# DCO_core_1_0.net
KiCad netlist of a schematic drawn in EAGLE
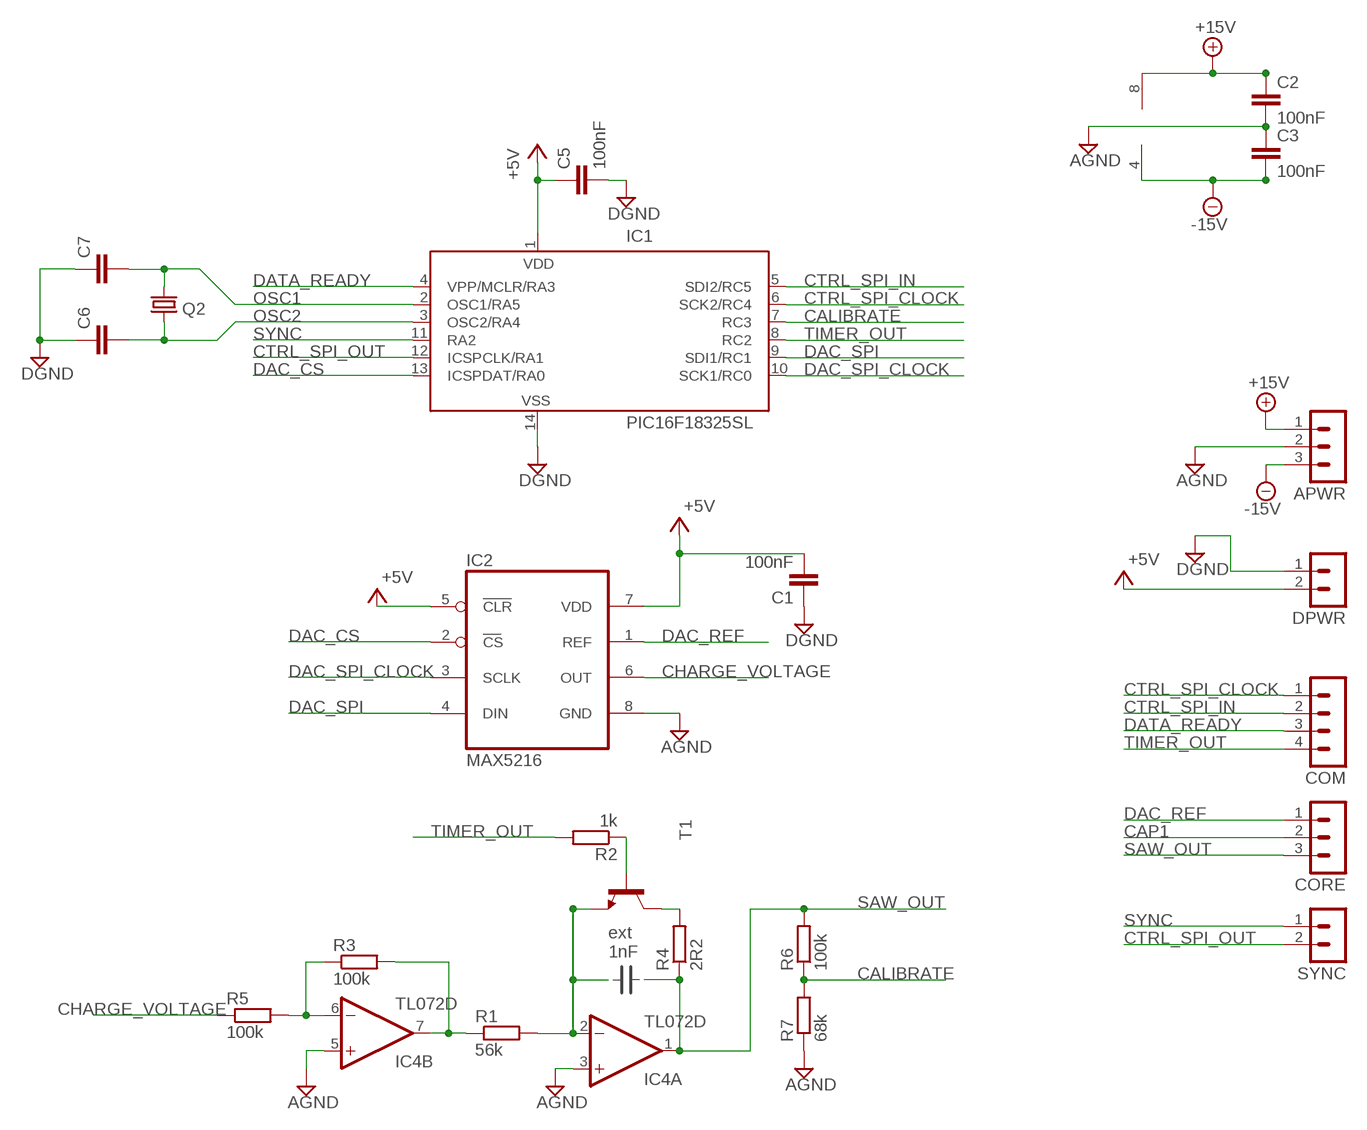
[diagram p0: schematic, sheet 1]

(export (version "E")
  (design (tool "Eeschema 10.0.6"))
  (components
    (comp (ref "APWR")
      (value "MA03-1JP")
      (footprint "eagle-import:SIP-PIN03-1J")
      (libsource (lib "eagle-import") (part "MA03-1JP"))
    )
    (comp (ref "C1")
      (value "100nF")
      (footprint "eagle-import:C0805")
      (libsource (lib "eagle-import") (part "C-EUC0805"))
    )
    (comp (ref "C2")
      (value "100nF")
      (footprint "eagle-import:C0805")
      (libsource (lib "eagle-import") (part "C-EUC0805"))
    )
    (comp (ref "C3")
      (value "100nF")
      (footprint "eagle-import:C0805")
      (libsource (lib "eagle-import") (part "C-EUC0805"))
    )
    (comp (ref "C5")
      (value "100nF")
      (footprint "eagle-import:C0805")
      (libsource (lib "eagle-import") (part "C-EUC0805"))
    )
    (comp (ref "C6")
      (value "C-EUC0805")
      (footprint "eagle-import:C0805")
      (libsource (lib "eagle-import") (part "C-EUC0805"))
    )
    (comp (ref "C7")
      (value "C-EUC0805")
      (footprint "eagle-import:C0805")
      (libsource (lib "eagle-import") (part "C-EUC0805"))
    )
    (comp (ref "COM")
      (value "MA04-1JP")
      (footprint "eagle-import:SIP-PIN04-1J")
      (libsource (lib "eagle-import") (part "MA04-1JP"))
    )
    (comp (ref "CORE")
      (value "MA03-1JP")
      (footprint "eagle-import:SIP-PIN03-1J")
      (libsource (lib "eagle-import") (part "MA03-1JP"))
    )
    (comp (ref "DPWR")
      (value "MA02-1JP")
      (footprint "eagle-import:SIP-PIN02-1J")
      (libsource (lib "eagle-import") (part "MA02-1JP"))
    )
    (comp (ref "IC1")
      (value "PIC16F18325SL")
      (footprint "eagle-import:SO14J")
      (fields (field (name "MF") "MICROCHIP") (field (name "MPN") "PIC16F676-I/SL"))
      (libsource (lib "eagle-import") (part "PIC16F18325SL"))
    )
    (comp (ref "IC2")
      (value "MAX5216")
      (footprint "eagle-import:UMAX8J")
      (libsource (lib "eagle-import") (part "MAX5216"))
    )
    (comp (ref "IC4")
      (value "TL072D")
      (footprint "eagle-import:SO08J")
      (libsource (lib "eagle-import") (part "TL072D"))
    )
    (comp (ref "Q2")
      (value "CRYSTALHC49S")
      (footprint "eagle-import:HC49_S")
      (libsource (lib "eagle-import") (part "CRYSTALHC49S"))
    )
    (comp (ref "R1")
      (value "56k")
      (footprint "eagle-import:R0805")
      (libsource (lib "eagle-import") (part "R-EU_R0805"))
    )
    (comp (ref "R2")
      (value "1k")
      (footprint "eagle-import:R0805")
      (libsource (lib "eagle-import") (part "R-EU_R0805"))
    )
    (comp (ref "R3")
      (value "100k")
      (footprint "eagle-import:R0805")
      (libsource (lib "eagle-import") (part "R-EU_R0805"))
    )
    (comp (ref "R4")
      (value "2R2")
      (footprint "eagle-import:R0805")
      (libsource (lib "eagle-import") (part "R-EU_R0805"))
    )
    (comp (ref "R5")
      (value "100k")
      (footprint "eagle-import:R0805")
      (libsource (lib "eagle-import") (part "R-EU_R0805"))
    )
    (comp (ref "R6")
      (value "100k")
      (footprint "eagle-import:R0805")
      (libsource (lib "eagle-import") (part "R-EU_R0805"))
    )
    (comp (ref "R7")
      (value "68k")
      (footprint "eagle-import:R0805")
      (libsource (lib "eagle-import") (part "R-EU_R0805"))
    )
    (comp (ref "SYNC")
      (value "MA02-1JP")
      (footprint "eagle-import:SIP-PIN02-1J")
      (libsource (lib "eagle-import") (part "MA02-1JP"))
    )
    (comp (ref "T1")
      (value "MMBT3904LT1-NPN-SOT23-BEC")
      (footprint "eagle-import:SOT23-BEC")
      (libsource (lib "eagle-import") (part "-NPN-SOT23-BECMMBT3904LT1"))
    )
  )
  (nets
    (net (code "1") (name "+5V") (class "Default")
      (node (ref "C1") (pin "2") (pinfunction "2_2") (pintype "passive"))
      (node (ref "C5") (pin "1") (pinfunction "1_1") (pintype "passive"))
      (node (ref "DPWR") (pin "2") (pinfunction "2_2") (pintype "passive"))
      (node (ref "IC1") (pin "1") (pinfunction "VDD_1") (pintype "power_in"))
      (node (ref "IC2") (pin "5") (pinfunction "CLR_5") (pintype "input"))
      (node (ref "IC2") (pin "7") (pinfunction "VDD_7") (pintype "power_in"))
    )
    (net (code "2") (name "+15V") (class "Default")
      (node (ref "APWR") (pin "1") (pinfunction "1_1") (pintype "passive"))
      (node (ref "C2") (pin "1") (pinfunction "1_1") (pintype "passive"))
      (node (ref "IC4") (pin "8") (pinfunction "V+_8") (pintype "power_in"))
    )
    (net (code "3") (name "-15V") (class "Default")
      (node (ref "APWR") (pin "3") (pinfunction "3_3") (pintype "passive"))
      (node (ref "C3") (pin "2") (pinfunction "2_2") (pintype "passive"))
      (node (ref "IC4") (pin "4") (pinfunction "V-_4") (pintype "power_in"))
    )
    (net (code "4") (name "/CALIBRATE") (class "Default")
      (node (ref "IC1") (pin "7") (pinfunction "RC3_7") (pintype "bidirectional"))
      (node (ref "R6") (pin "1") (pinfunction "1_1") (pintype "passive"))
      (node (ref "R7") (pin "2") (pinfunction "2_2") (pintype "passive"))
    )
    (net (code "5") (name "/CAP1") (class "Default")
      (node (ref "CORE") (pin "2") (pinfunction "2_2") (pintype "passive"))
      (node (ref "IC4") (pin "2") (pinfunction "-IN_2") (pintype "input"))
      (node (ref "R1") (pin "2") (pinfunction "2_2") (pintype "passive"))
      (node (ref "T1") (pin "E") (pinfunction "E_E") (pintype "passive"))
    )
    (net (code "6") (name "/CHARGE_VOLTAGE") (class "Default")
      (node (ref "IC2") (pin "6") (pinfunction "OUT_6") (pintype "power_in"))
      (node (ref "R5") (pin "1") (pinfunction "1_1") (pintype "passive"))
    )
    (net (code "7") (name "/CTRL_SPI_CLOCK") (class "Default")
      (node (ref "COM") (pin "1") (pinfunction "1_1") (pintype "passive"))
      (node (ref "IC1") (pin "6") (pinfunction "SCK2/RC4_6") (pintype "bidirectional"))
    )
    (net (code "8") (name "/CTRL_SPI_IN") (class "Default")
      (node (ref "COM") (pin "2") (pinfunction "2_2") (pintype "passive"))
      (node (ref "IC1") (pin "5") (pinfunction "SDI2/RC5_5") (pintype "bidirectional"))
    )
    (net (code "9") (name "/CTRL_SPI_OUT") (class "Default")
      (node (ref "IC1") (pin "12") (pinfunction "ICSPCLK/RA1_12") (pintype "bidirectional"))
      (node (ref "SYNC") (pin "2") (pinfunction "2_2") (pintype "passive"))
    )
    (net (code "10") (name "/DAC_CS") (class "Default")
      (node (ref "IC1") (pin "13") (pinfunction "ICSPDAT/RA0_13") (pintype "bidirectional"))
      (node (ref "IC2") (pin "2") (pinfunction "CS_2") (pintype "input"))
    )
    (net (code "11") (name "/DAC_REF") (class "Default")
      (node (ref "CORE") (pin "1") (pinfunction "1_1") (pintype "passive"))
      (node (ref "IC2") (pin "1") (pinfunction "REF_1") (pintype "input"))
    )
    (net (code "12") (name "/DAC_SPI") (class "Default")
      (node (ref "IC1") (pin "9") (pinfunction "SDI1/RC1_9") (pintype "bidirectional"))
      (node (ref "IC2") (pin "4") (pinfunction "DIN_4") (pintype "input"))
    )
    (net (code "13") (name "/DAC_SPI_CLOCK") (class "Default")
      (node (ref "IC1") (pin "10") (pinfunction "SCK1/RC0_10") (pintype "bidirectional"))
      (node (ref "IC2") (pin "3") (pinfunction "SCLK_3") (pintype "input"))
    )
    (net (code "14") (name "/DATA_READY") (class "Default")
      (node (ref "COM") (pin "3") (pinfunction "3_3") (pintype "passive"))
      (node (ref "IC1") (pin "4") (pinfunction "VPP/MCLR/RA3_4") (pintype "input"))
    )
    (net (code "15") (name "/OSC1") (class "Default")
      (node (ref "C7") (pin "2") (pinfunction "2_2") (pintype "passive"))
      (node (ref "IC1") (pin "2") (pinfunction "OSC1/RA5_2") (pintype "bidirectional"))
      (node (ref "Q2") (pin "2") (pinfunction "2_2") (pintype "passive"))
    )
    (net (code "16") (name "/OSC2") (class "Default")
      (node (ref "C6") (pin "2") (pinfunction "2_2") (pintype "passive"))
      (node (ref "IC1") (pin "3") (pinfunction "OSC2/RA4_3") (pintype "bidirectional"))
      (node (ref "Q2") (pin "1") (pinfunction "1_1") (pintype "passive"))
    )
    (net (code "17") (name "/SAW_OUT") (class "Default")
      (node (ref "CORE") (pin "3") (pinfunction "3_3") (pintype "passive"))
      (node (ref "IC4") (pin "1") (pinfunction "OUT_1") (pintype "output"))
      (node (ref "R4") (pin "1") (pinfunction "1_1") (pintype "passive"))
      (node (ref "R6") (pin "2") (pinfunction "2_2") (pintype "passive"))
    )
    (net (code "18") (name "/SYNC") (class "Default")
      (node (ref "IC1") (pin "11") (pinfunction "RA2_11") (pintype "bidirectional"))
      (node (ref "SYNC") (pin "1") (pinfunction "1_1") (pintype "passive"))
    )
    (net (code "19") (name "/TIMER_OUT") (class "Default")
      (node (ref "COM") (pin "4") (pinfunction "4_4") (pintype "passive"))
      (node (ref "IC1") (pin "8") (pinfunction "RC2_8") (pintype "bidirectional"))
      (node (ref "R2") (pin "2") (pinfunction "2_2") (pintype "passive"))
    )
    (net (code "20") (name "AGND") (class "Default")
      (node (ref "APWR") (pin "2") (pinfunction "2_2") (pintype "passive"))
      (node (ref "C2") (pin "2") (pinfunction "2_2") (pintype "passive"))
      (node (ref "C3") (pin "1") (pinfunction "1_1") (pintype "passive"))
      (node (ref "IC2") (pin "8") (pinfunction "GND_8") (pintype "power_in"))
      (node (ref "IC4") (pin "3") (pinfunction "+IN_3") (pintype "input"))
      (node (ref "IC4") (pin "5") (pinfunction "+IN_5") (pintype "input"))
      (node (ref "R7") (pin "1") (pinfunction "1_1") (pintype "passive"))
    )
    (net (code "21") (name "DGND") (class "Default")
      (node (ref "C1") (pin "1") (pinfunction "1_1") (pintype "passive"))
      (node (ref "C5") (pin "2") (pinfunction "2_2") (pintype "passive"))
      (node (ref "C6") (pin "1") (pinfunction "1_1") (pintype "passive"))
      (node (ref "C7") (pin "1") (pinfunction "1_1") (pintype "passive"))
      (node (ref "DPWR") (pin "1") (pinfunction "1_1") (pintype "passive"))
      (node (ref "IC1") (pin "14") (pinfunction "VSS_14") (pintype "power_in"))
    )
    (net (code "22") (name "Net-(IC4B--IN)") (class "Default")
      (node (ref "IC4") (pin "6") (pinfunction "-IN_6") (pintype "input"))
      (node (ref "R3") (pin "1") (pinfunction "1_1") (pintype "passive"))
      (node (ref "R5") (pin "2") (pinfunction "2_2") (pintype "passive"))
    )
    (net (code "23") (name "Net-(IC4B-OUT)") (class "Default")
      (node (ref "IC4") (pin "7") (pinfunction "OUT_7") (pintype "output"))
      (node (ref "R1") (pin "1") (pinfunction "1_1") (pintype "passive"))
      (node (ref "R3") (pin "2") (pinfunction "2_2") (pintype "passive"))
    )
    (net (code "24") (name "Net-(R2-Pad1)") (class "Default")
      (node (ref "R2") (pin "1") (pinfunction "1_1") (pintype "passive"))
      (node (ref "T1") (pin "B") (pinfunction "B_B") (pintype "passive"))
    )
    (net (code "25") (name "Net-(R4-Pad2)") (class "Default")
      (node (ref "R4") (pin "2") (pinfunction "2_2") (pintype "passive"))
      (node (ref "T1") (pin "C") (pinfunction "C_C") (pintype "passive"))
    )
  )
)
